# wiring_thermography.net
KiCad netlist of a schematic drawn in EAGLE
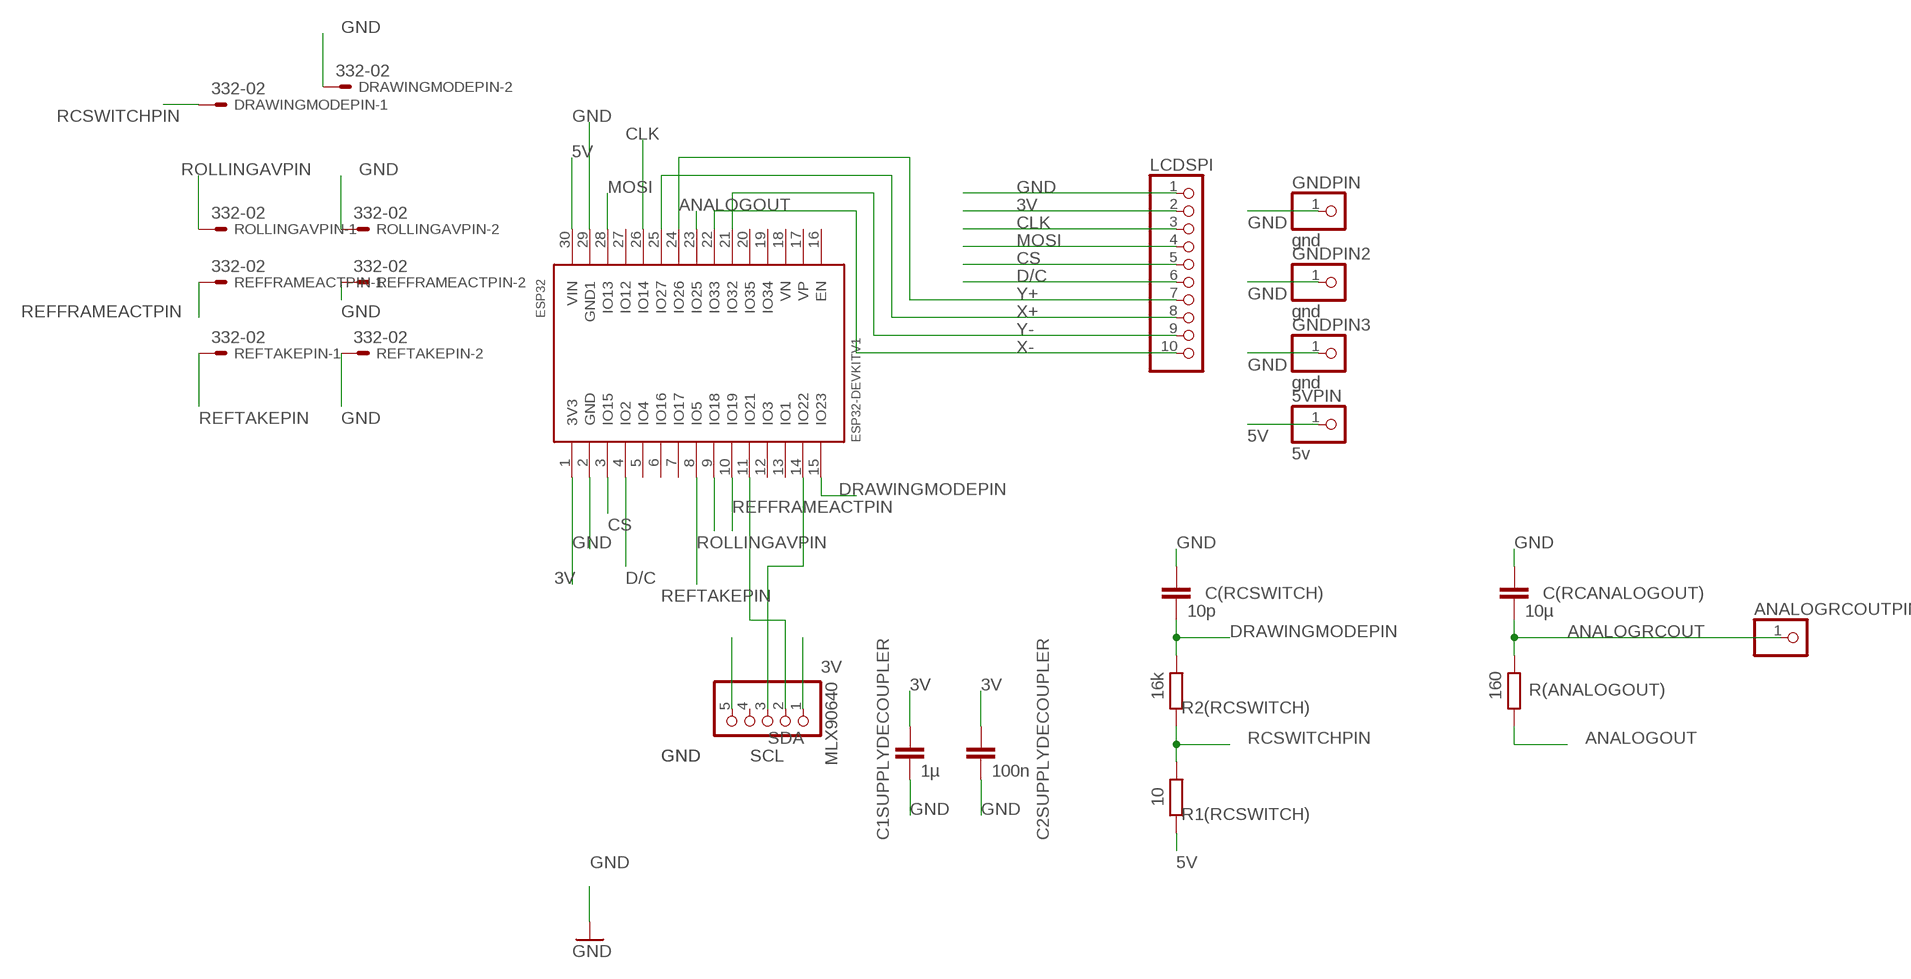
[diagram p0: schematic, sheet 1]

(export (version "E")
  (design (tool "Eeschema 10.0.6"))
  (components
    (comp (ref "5VPIN")
      (value "5v")
      (footprint "eagle-import:1X01")
      (libsource (lib "eagle-import") (part "PINHD-1X1"))
    )
    (comp (ref "ANALOGRCOUTPIN")
      (value "PINHD-1X1")
      (footprint "eagle-import:1X01")
      (libsource (lib "eagle-import") (part "PINHD-1X1"))
    )
    (comp (ref "C(RCANALOGOUT)")
      (value "10µ")
      (footprint "eagle-import:C5B5")
      (libsource (lib "eagle-import") (part "C5/5"))
    )
    (comp (ref "C(RCSWITCH)")
      (value "10p")
      (footprint "eagle-import:C5B5")
      (libsource (lib "eagle-import") (part "C5/5"))
    )
    (comp (ref "C1SUPPLYDECOUPLER")
      (value "1µ")
      (footprint "eagle-import:C5B5")
      (libsource (lib "eagle-import") (part "C5/5"))
    )
    (comp (ref "C2SUPPLYDECOUPLER")
      (value "100n")
      (footprint "eagle-import:C5B5")
      (libsource (lib "eagle-import") (part "C5/5"))
    )
    (comp (ref "DRAWINGMODEPIN")
      (value "332-02")
      (footprint "eagle-import:332-02")
      (libsource (lib "eagle-import") (part "332-02"))
    )
    (comp (ref "ESP32")
      (value "ESP32DEVKITV1")
      (footprint "eagle-import:ESP32-DEVKITV1")
      (libsource (lib "eagle-import") (part "ESP32DEVKITV1"))
    )
    (comp (ref "GNDPIN")
      (value "gnd")
      (footprint "eagle-import:1X01")
      (libsource (lib "eagle-import") (part "PINHD-1X1"))
    )
    (comp (ref "GNDPIN2")
      (value "gnd")
      (footprint "eagle-import:1X01")
      (libsource (lib "eagle-import") (part "PINHD-1X1"))
    )
    (comp (ref "GNDPIN3")
      (value "gnd")
      (footprint "eagle-import:1X01")
      (libsource (lib "eagle-import") (part "PINHD-1X1"))
    )
    (comp (ref "LCDSPI")
      (value "PINHD-1X10")
      (footprint "eagle-import:1X10")
      (libsource (lib "eagle-import") (part "PINHD-1X10"))
    )
    (comp (ref "MLX90640")
      (value "PINHD-1X5")
      (footprint "eagle-import:1X05")
      (libsource (lib "eagle-import") (part "PINHD-1X5"))
    )
    (comp (ref "R(ANALOGOUT)")
      (value "160")
      (footprint "eagle-import:0207_7")
      (libsource (lib "eagle-import") (part "R-EU_0207/7"))
    )
    (comp (ref "R1(RCSWITCH)")
      (value "10")
      (footprint "eagle-import:0207_7")
      (libsource (lib "eagle-import") (part "R-EU_0207/7"))
    )
    (comp (ref "R2(RCSWITCH)")
      (value "16k")
      (footprint "eagle-import:0207_7")
      (libsource (lib "eagle-import") (part "R-EU_0207/7"))
    )
    (comp (ref "REFFRAMEACTPIN")
      (value "332-02")
      (footprint "eagle-import:332-02")
      (libsource (lib "eagle-import") (part "332-02"))
    )
    (comp (ref "REFTAKEPIN")
      (value "332-02")
      (footprint "eagle-import:332-02")
      (libsource (lib "eagle-import") (part "332-02"))
    )
    (comp (ref "ROLLINGAVPIN")
      (value "332-02")
      (footprint "eagle-import:332-02")
      (libsource (lib "eagle-import") (part "332-02"))
    )
  )
  (nets
    (net (code "1") (name "/3V") (class "Default")
      (node (ref "C1SUPPLYDECOUPLER") (pin "1") (pinfunction "1_1") (pintype "passive"))
      (node (ref "C2SUPPLYDECOUPLER") (pin "1") (pinfunction "1_1") (pintype "passive"))
      (node (ref "ESP32") (pin "1") (pinfunction "3V3_1") (pintype "bidirectional"))
      (node (ref "LCDSPI") (pin "2") (pinfunction "2_2") (pintype "passive"))
      (node (ref "MLX90640") (pin "1") (pinfunction "1_1") (pintype "passive"))
    )
    (net (code "2") (name "/5V") (class "Default")
      (node (ref "5VPIN") (pin "1") (pinfunction "1_1") (pintype "passive"))
      (node (ref "ESP32") (pin "30") (pinfunction "VIN_30") (pintype "bidirectional"))
      (node (ref "R1(RCSWITCH)") (pin "1") (pinfunction "1_1") (pintype "passive"))
    )
    (net (code "3") (name "/ANALOGOUT") (class "Default")
      (node (ref "ESP32") (pin "23") (pinfunction "IO25_23") (pintype "bidirectional"))
      (node (ref "R(ANALOGOUT)") (pin "1") (pinfunction "1_1") (pintype "passive"))
    )
    (net (code "4") (name "/ANALOGRCOUT") (class "Default")
      (node (ref "ANALOGRCOUTPIN") (pin "1") (pinfunction "1_1") (pintype "passive"))
      (node (ref "C(RCANALOGOUT)") (pin "2") (pinfunction "2_2") (pintype "passive"))
      (node (ref "R(ANALOGOUT)") (pin "2") (pinfunction "2_2") (pintype "passive"))
    )
    (net (code "5") (name "/CLK") (class "Default")
      (node (ref "ESP32") (pin "26") (pinfunction "IO14_26") (pintype "bidirectional"))
      (node (ref "LCDSPI") (pin "3") (pinfunction "3_3") (pintype "passive"))
    )
    (net (code "6") (name "/CS") (class "Default")
      (node (ref "ESP32") (pin "3") (pinfunction "IO15_3") (pintype "bidirectional"))
      (node (ref "LCDSPI") (pin "5") (pinfunction "5_5") (pintype "passive"))
    )
    (net (code "7") (name "/DRAWINGMODEPIN") (class "Default")
      (node (ref "C(RCSWITCH)") (pin "2") (pinfunction "2_2") (pintype "passive"))
      (node (ref "ESP32") (pin "15") (pinfunction "IO23_15") (pintype "bidirectional"))
      (node (ref "R2(RCSWITCH)") (pin "2") (pinfunction "2_2") (pintype "passive"))
    )
    (net (code "8") (name "/D{slash}C") (class "Default")
      (node (ref "ESP32") (pin "4") (pinfunction "IO2_4") (pintype "bidirectional"))
      (node (ref "LCDSPI") (pin "6") (pinfunction "6_6") (pintype "passive"))
    )
    (net (code "9") (name "/MOSI") (class "Default")
      (node (ref "ESP32") (pin "28") (pinfunction "IO13_28") (pintype "bidirectional"))
      (node (ref "LCDSPI") (pin "4") (pinfunction "4_4") (pintype "passive"))
    )
    (net (code "10") (name "/RCSWITCHPIN") (class "Default")
      (node (ref "DRAWINGMODEPIN") (pin "1") (pinfunction "S_1") (pintype "passive"))
      (node (ref "R1(RCSWITCH)") (pin "2") (pinfunction "2_2") (pintype "passive"))
      (node (ref "R2(RCSWITCH)") (pin "1") (pinfunction "1_1") (pintype "passive"))
    )
    (net (code "11") (name "/REFFRAMEACTPIN") (class "Default")
      (node (ref "ESP32") (pin "10") (pinfunction "IO19_10") (pintype "bidirectional"))
      (node (ref "REFFRAMEACTPIN") (pin "1") (pinfunction "S_1") (pintype "passive"))
    )
    (net (code "12") (name "/REFTAKEPIN") (class "Default")
      (node (ref "ESP32") (pin "8") (pinfunction "IO5_8") (pintype "bidirectional"))
      (node (ref "REFTAKEPIN") (pin "1") (pinfunction "S_1") (pintype "passive"))
    )
    (net (code "13") (name "/ROLLINGAVPIN") (class "Default")
      (node (ref "ESP32") (pin "9") (pinfunction "IO18_9") (pintype "bidirectional"))
      (node (ref "ROLLINGAVPIN") (pin "1") (pinfunction "S_1") (pintype "passive"))
    )
    (net (code "14") (name "/SCL") (class "Default")
      (node (ref "ESP32") (pin "14") (pinfunction "IO22_14") (pintype "bidirectional"))
      (node (ref "MLX90640") (pin "3") (pinfunction "3_3") (pintype "passive"))
    )
    (net (code "15") (name "/SDA") (class "Default")
      (node (ref "ESP32") (pin "11") (pinfunction "IO21_11") (pintype "bidirectional"))
      (node (ref "MLX90640") (pin "2") (pinfunction "2_2") (pintype "passive"))
    )
    (net (code "16") (name "/X+") (class "Default")
      (node (ref "ESP32") (pin "25") (pinfunction "IO27_25") (pintype "bidirectional"))
      (node (ref "LCDSPI") (pin "8") (pinfunction "8_8") (pintype "passive"))
    )
    (net (code "17") (name "/X-") (class "Default")
      (node (ref "ESP32") (pin "22") (pinfunction "IO33_22") (pintype "bidirectional"))
      (node (ref "LCDSPI") (pin "10") (pinfunction "10_10") (pintype "passive"))
    )
    (net (code "18") (name "/Y+") (class "Default")
      (node (ref "ESP32") (pin "24") (pinfunction "IO26_24") (pintype "bidirectional"))
      (node (ref "LCDSPI") (pin "7") (pinfunction "7_7") (pintype "passive"))
    )
    (net (code "19") (name "/Y-") (class "Default")
      (node (ref "ESP32") (pin "21") (pinfunction "IO32_21") (pintype "bidirectional"))
      (node (ref "LCDSPI") (pin "9") (pinfunction "9_9") (pintype "passive"))
    )
    (net (code "20") (name "GND") (class "Default")
      (node (ref "C(RCANALOGOUT)") (pin "1") (pinfunction "1_1") (pintype "passive"))
      (node (ref "C(RCSWITCH)") (pin "1") (pinfunction "1_1") (pintype "passive"))
      (node (ref "C1SUPPLYDECOUPLER") (pin "2") (pinfunction "2_2") (pintype "passive"))
      (node (ref "C2SUPPLYDECOUPLER") (pin "2") (pinfunction "2_2") (pintype "passive"))
      (node (ref "DRAWINGMODEPIN") (pin "2") (pinfunction "S_2") (pintype "passive"))
      (node (ref "ESP32") (pin "2") (pinfunction "GND_2") (pintype "bidirectional"))
      (node (ref "ESP32") (pin "29") (pinfunction "GND1_29") (pintype "bidirectional"))
      (node (ref "GNDPIN") (pin "1") (pinfunction "1_1") (pintype "passive"))
      (node (ref "GNDPIN2") (pin "1") (pinfunction "1_1") (pintype "passive"))
      (node (ref "GNDPIN3") (pin "1") (pinfunction "1_1") (pintype "passive"))
      (node (ref "LCDSPI") (pin "1") (pinfunction "1_1") (pintype "passive"))
      (node (ref "MLX90640") (pin "5") (pinfunction "5_5") (pintype "passive"))
      (node (ref "REFFRAMEACTPIN") (pin "2") (pinfunction "S_2") (pintype "passive"))
      (node (ref "REFTAKEPIN") (pin "2") (pinfunction "S_2") (pintype "passive"))
      (node (ref "ROLLINGAVPIN") (pin "2") (pinfunction "S_2") (pintype "passive"))
    )
    (net (code "21") (name "unconnected-(ESP32-EN-Pad16)") (class "Default")
      (node (ref "ESP32") (pin "16") (pinfunction "EN_16") (pintype "bidirectional"))
    )
    (net (code "22") (name "unconnected-(ESP32-IO1-Pad13)") (class "Default")
      (node (ref "ESP32") (pin "13") (pinfunction "IO1_13") (pintype "bidirectional"))
    )
    (net (code "23") (name "unconnected-(ESP32-IO3-Pad12)") (class "Default")
      (node (ref "ESP32") (pin "12") (pinfunction "IO3_12") (pintype "bidirectional"))
    )
    (net (code "24") (name "unconnected-(ESP32-IO4-Pad5)") (class "Default")
      (node (ref "ESP32") (pin "5") (pinfunction "IO4_5") (pintype "bidirectional"))
    )
    (net (code "25") (name "unconnected-(ESP32-IO12-Pad27)") (class "Default")
      (node (ref "ESP32") (pin "27") (pinfunction "IO12_27") (pintype "bidirectional"))
    )
    (net (code "26") (name "unconnected-(ESP32-IO16-Pad6)") (class "Default")
      (node (ref "ESP32") (pin "6") (pinfunction "IO16_6") (pintype "bidirectional"))
    )
    (net (code "27") (name "unconnected-(ESP32-IO17-Pad7)") (class "Default")
      (node (ref "ESP32") (pin "7") (pinfunction "IO17_7") (pintype "bidirectional"))
    )
    (net (code "28") (name "unconnected-(ESP32-IO34-Pad19)") (class "Default")
      (node (ref "ESP32") (pin "19") (pinfunction "IO34_19") (pintype "bidirectional"))
    )
    (net (code "29") (name "unconnected-(ESP32-IO35-Pad20)") (class "Default")
      (node (ref "ESP32") (pin "20") (pinfunction "IO35_20") (pintype "bidirectional"))
    )
    (net (code "30") (name "unconnected-(ESP32-VN-Pad18)") (class "Default")
      (node (ref "ESP32") (pin "18") (pinfunction "VN_18") (pintype "bidirectional"))
    )
    (net (code "31") (name "unconnected-(ESP32-VP-Pad17)") (class "Default")
      (node (ref "ESP32") (pin "17") (pinfunction "VP_17") (pintype "bidirectional"))
    )
    (net (code "32") (name "unconnected-(MLX90640-Pad4)") (class "Default")
      (node (ref "MLX90640") (pin "4") (pinfunction "4_4") (pintype "passive"))
    )
  )
)
